# DSO_RAM.net
KiCad netlist of a schematic drawn in Altium Designer
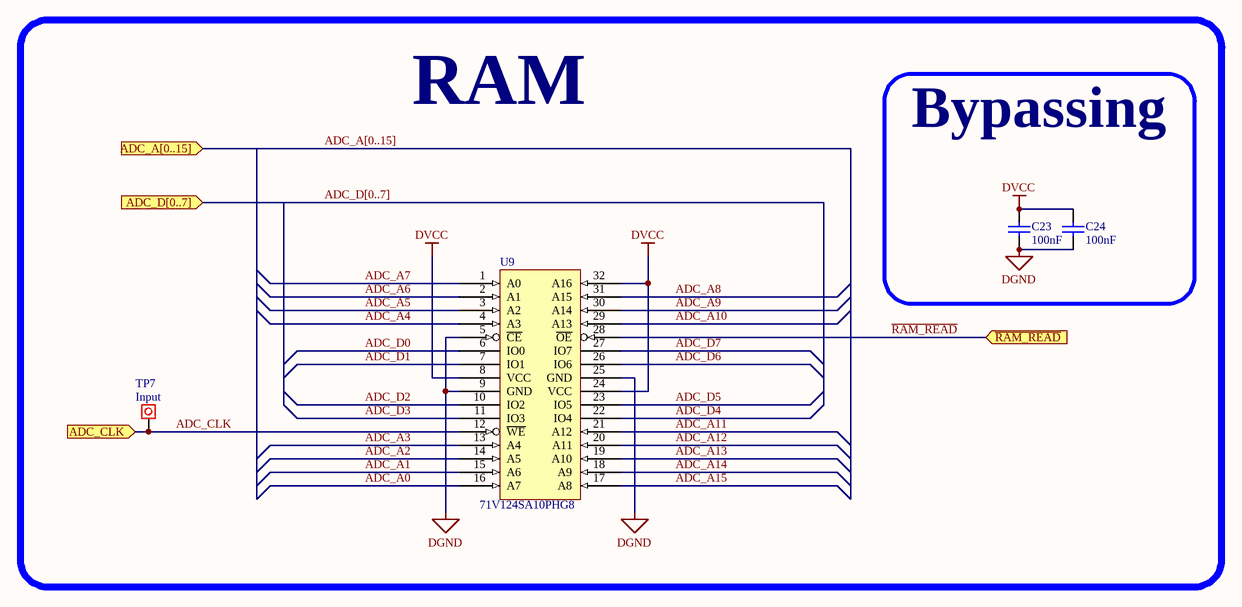
[diagram p0: DSO_RAM.SchDoc]

(export (version "E")
  (design (tool "Eeschema 10.0.6"))
  (components
    (comp (ref "C23")
      (value "100nF")
      (footprint "0805C")
      (description "Capacitor")
      (fields (field (name "REVIEWED BY") "RM - 2018/08/05"))
      (libsource (lib "DSO") (part "C"))
    )
    (comp (ref "C24")
      (value "100nF")
      (footprint "0805C")
      (description "Capacitor")
      (fields (field (name "REVIEWED BY") "RM - 2018/08/05"))
      (libsource (lib "DSO") (part "C"))
    )
    (comp (ref "TP7")
      (value "Input")
      (footprint "Testpoin")
      (description "Pad")
      (fields (field (name "Comment") "INPUT"))
      (libsource (lib "DSO") (part "Test Point"))
    )
    (comp (ref "U9")
      (value "71V124SA10PHG8")
      (footprint "TSOP-32")
      (description "SRAM 128k x 8")
      (fields (field (name "REVIEWED BY") "RM - 2018/08/05"))
      (libsource (lib "DSO") (part "CY7C1019D"))
    )
  )
  (nets
    (net (code "1") (name "/ADC_A0") (class "Default")
      (node (ref "U9") (pin "16") (pinfunction "A7_16") (pintype "input"))
    )
    (net (code "2") (name "/ADC_A1") (class "Default")
      (node (ref "U9") (pin "15") (pinfunction "A6_15") (pintype "input"))
    )
    (net (code "3") (name "/ADC_A2") (class "Default")
      (node (ref "U9") (pin "14") (pinfunction "A5_14") (pintype "input"))
    )
    (net (code "4") (name "/ADC_A3") (class "Default")
      (node (ref "U9") (pin "13") (pinfunction "A4_13") (pintype "input"))
    )
    (net (code "5") (name "/ADC_A4") (class "Default")
      (node (ref "U9") (pin "4") (pinfunction "A3_4") (pintype "input"))
    )
    (net (code "6") (name "/ADC_A5") (class "Default")
      (node (ref "U9") (pin "3") (pinfunction "A2_3") (pintype "input"))
    )
    (net (code "7") (name "/ADC_A6") (class "Default")
      (node (ref "U9") (pin "2") (pinfunction "A1_2") (pintype "input"))
    )
    (net (code "8") (name "/ADC_A7") (class "Default")
      (node (ref "U9") (pin "1") (pinfunction "A0_1") (pintype "input"))
    )
    (net (code "9") (name "/ADC_A8") (class "Default")
      (node (ref "U9") (pin "31") (pinfunction "A15_31") (pintype "input"))
    )
    (net (code "10") (name "/ADC_A9") (class "Default")
      (node (ref "U9") (pin "30") (pinfunction "A14_30") (pintype "input"))
    )
    (net (code "11") (name "/ADC_A10") (class "Default")
      (node (ref "U9") (pin "29") (pinfunction "A13_29") (pintype "input"))
    )
    (net (code "12") (name "/ADC_A11") (class "Default")
      (node (ref "U9") (pin "21") (pinfunction "A12_21") (pintype "input"))
    )
    (net (code "13") (name "/ADC_A12") (class "Default")
      (node (ref "U9") (pin "20") (pinfunction "A11_20") (pintype "input"))
    )
    (net (code "14") (name "/ADC_A13") (class "Default")
      (node (ref "U9") (pin "19") (pinfunction "A10_19") (pintype "input"))
    )
    (net (code "15") (name "/ADC_A14") (class "Default")
      (node (ref "U9") (pin "18") (pinfunction "A9_18") (pintype "input"))
    )
    (net (code "16") (name "/ADC_A15") (class "Default")
      (node (ref "U9") (pin "17") (pinfunction "A8_17") (pintype "input"))
    )
    (net (code "18") (name "/ADC_CLK") (class "Default")
      (node (ref "TP7") (pin "1") (pintype "passive"))
      (node (ref "U9") (pin "12") (pinfunction "~{WE}_12") (pintype "input"))
    )
    (net (code "19") (name "/ADC_D0") (class "Default")
      (node (ref "U9") (pin "6") (pinfunction "IO0_6") (pintype "tri_state"))
    )
    (net (code "20") (name "/ADC_D1") (class "Default")
      (node (ref "U9") (pin "7") (pinfunction "IO1_7") (pintype "tri_state"))
    )
    (net (code "21") (name "/ADC_D2") (class "Default")
      (node (ref "U9") (pin "10") (pinfunction "IO2_10") (pintype "tri_state"))
    )
    (net (code "22") (name "/ADC_D3") (class "Default")
      (node (ref "U9") (pin "11") (pinfunction "IO3_11") (pintype "tri_state"))
    )
    (net (code "23") (name "/ADC_D4") (class "Default")
      (node (ref "U9") (pin "22") (pinfunction "IO4_22") (pintype "tri_state"))
    )
    (net (code "24") (name "/ADC_D5") (class "Default")
      (node (ref "U9") (pin "23") (pinfunction "IO5_23") (pintype "tri_state"))
    )
    (net (code "25") (name "/ADC_D6") (class "Default")
      (node (ref "U9") (pin "26") (pinfunction "IO6_26") (pintype "tri_state"))
    )
    (net (code "26") (name "/ADC_D7") (class "Default")
      (node (ref "U9") (pin "27") (pinfunction "IO7_27") (pintype "tri_state"))
    )
    (net (code "28") (name "/~{RAM_READ}") (class "Default")
      (node (ref "U9") (pin "28") (pinfunction "~{OE}_28") (pintype "input"))
    )
    (net (code "29") (name "DGND") (class "Default")
      (node (ref "C23") (pin "2") (pinfunction "2_2") (pintype "passive"))
      (node (ref "C24") (pin "2") (pinfunction "2_2") (pintype "passive"))
      (node (ref "U9") (pin "25") (pinfunction "GND_25") (pintype "passive"))
      (node (ref "U9") (pin "5") (pinfunction "~{CE}_5") (pintype "input"))
      (node (ref "U9") (pin "9") (pinfunction "GND_9") (pintype "passive"))
    )
    (net (code "30") (name "DVCC") (class "Default")
      (node (ref "C23") (pin "1") (pinfunction "1_1") (pintype "passive"))
      (node (ref "C24") (pin "1") (pinfunction "1_1") (pintype "passive"))
      (node (ref "U9") (pin "24") (pinfunction "VCC_24") (pintype "passive"))
      (node (ref "U9") (pin "32") (pinfunction "A16_32") (pintype "input"))
      (node (ref "U9") (pin "8") (pinfunction "VCC_8") (pintype "passive"))
    )
  )
)
